# i2-mb_rpi.net
KiCad netlist of a schematic drawn in EAGLE
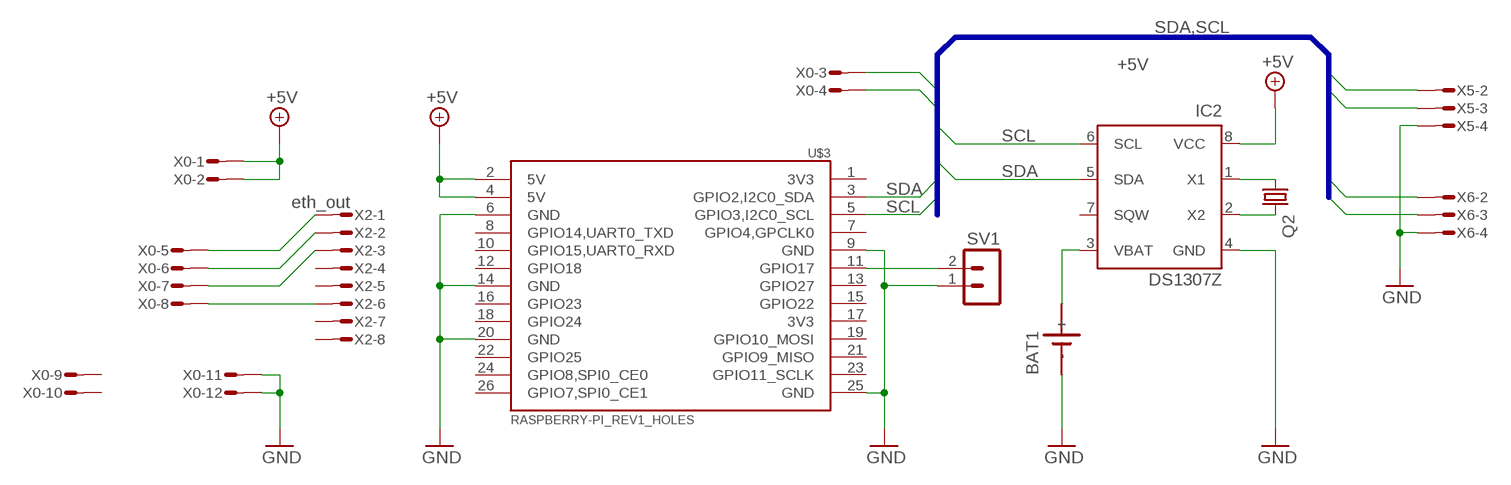
[diagram p0: schematic, sheet 1]

(export (version "E")
  (design (tool "Eeschema 10.0.6"))
  (components
    (comp (ref "BAT1")
      (value "SN2032")
      (footprint "eagle-import:SN2032")
      (libsource (lib "eagle-import") (part "SN2032"))
    )
    (comp (ref "IC2")
      (value "DS1307Z")
      (footprint "eagle-import:SOIC8")
      (libsource (lib "eagle-import") (part "DS1307Z"))
    )
    (comp (ref "Q2")
      (value "CRYSTAL")
      (footprint "eagle-import:CFPX-217")
      (libsource (lib "eagle-import") (part "CRYSTAL"))
    )
    (comp (ref "SV1")
      (value "MA02-1")
      (footprint "eagle-import:MA03-1")
      (libsource (lib "eagle-import") (part "MA02-1"))
    )
    (comp (ref "U$3")
      (value "RASPBERRY-PI_REV1_HOLES")
      (footprint "eagle-import:RASPBERRY-PI_REV1_HOLES")
      (libsource (lib "eagle-import") (part "RASPBERRY-PI_REV1_HOLES"))
    )
    (comp (ref "X0")
      (value "MICROMATCH-12")
      (footprint "eagle-import:MICROMATCH-12")
      (libsource (lib "eagle-import") (part "MICROMATCH-12"))
    )
    (comp (ref "X2")
      (value "eth_out")
      (footprint "eagle-import:MICROMATCH-8")
      (libsource (lib "eagle-import") (part "MICROMATCH-8"))
    )
    (comp (ref "X5")
      (value "i2c#1")
      (footprint "eagle-import:MICROMATCH-4")
      (libsource (lib "eagle-import") (part "MICROMATCH-4"))
    )
    (comp (ref "X6")
      (value "i2c#2")
      (footprint "eagle-import:MICROMATCH-4")
      (libsource (lib "eagle-import") (part "MICROMATCH-4"))
    )
  )
  (nets
    (net (code "1") (name "+5V") (class "Default")
      (node (ref "IC2") (pin "8") (pinfunction "VCC_8") (pintype "power_in"))
      (node (ref "U$3") (pin "2") (pinfunction "5V_2") (pintype "bidirectional"))
      (node (ref "U$3") (pin "4") (pinfunction "5V_4") (pintype "bidirectional"))
      (node (ref "X0") (pin "1") (pinfunction "S_1") (pintype "passive"))
      (node (ref "X0") (pin "2") (pinfunction "S_2") (pintype "passive"))
    )
    (net (code "2") (name "/SCL") (class "Default")
      (node (ref "IC2") (pin "6") (pinfunction "SCL_6") (pintype "input"))
      (node (ref "U$3") (pin "5") (pinfunction "GPIO3,I2C0_SCL_5") (pintype "bidirectional"))
      (node (ref "X0") (pin "4") (pinfunction "S_4") (pintype "passive"))
      (node (ref "X5") (pin "3") (pinfunction "S_3") (pintype "passive"))
      (node (ref "X6") (pin "3") (pinfunction "S_3") (pintype "passive"))
    )
    (net (code "3") (name "/SDA") (class "Default")
      (node (ref "IC2") (pin "5") (pinfunction "SDA_5") (pintype "bidirectional"))
      (node (ref "U$3") (pin "3") (pinfunction "GPIO2,I2C0_SDA_3") (pintype "bidirectional"))
      (node (ref "X0") (pin "3") (pinfunction "S_3") (pintype "passive"))
      (node (ref "X5") (pin "2") (pinfunction "S_2") (pintype "passive"))
      (node (ref "X6") (pin "2") (pinfunction "S_2") (pintype "passive"))
    )
    (net (code "5") (name "GND") (class "Default")
      (node (ref "BAT1") (pin "-") (pinfunction "-_-") (pintype "passive"))
      (node (ref "IC2") (pin "4") (pinfunction "GND_4") (pintype "power_in"))
      (node (ref "SV1") (pin "1") (pinfunction "1_1") (pintype "passive"))
      (node (ref "U$3") (pin "14") (pinfunction "GND_14") (pintype "bidirectional"))
      (node (ref "U$3") (pin "20") (pinfunction "GND_20") (pintype "bidirectional"))
      (node (ref "U$3") (pin "25") (pinfunction "GND_25") (pintype "bidirectional"))
      (node (ref "U$3") (pin "6") (pinfunction "GND_6") (pintype "bidirectional"))
      (node (ref "U$3") (pin "9") (pinfunction "GND_9") (pintype "bidirectional"))
      (node (ref "X0") (pin "11") (pinfunction "S_11") (pintype "passive"))
      (node (ref "X0") (pin "12") (pinfunction "S_12") (pintype "passive"))
      (node (ref "X5") (pin "4") (pinfunction "S_4") (pintype "passive"))
      (node (ref "X6") (pin "4") (pinfunction "S_4") (pintype "passive"))
    )
    (net (code "6") (name "Net-(IC2-VBAT)") (class "Default")
      (node (ref "BAT1") (pin "+") (pinfunction "+_+") (pintype "passive"))
      (node (ref "IC2") (pin "3") (pinfunction "VBAT_3") (pintype "passive"))
    )
    (net (code "7") (name "Net-(IC2-X1)") (class "Default")
      (node (ref "IC2") (pin "1") (pinfunction "X1_1") (pintype "input"))
      (node (ref "Q2") (pin "1") (pinfunction "1_1") (pintype "passive"))
    )
    (net (code "8") (name "Net-(IC2-X2)") (class "Default")
      (node (ref "IC2") (pin "2") (pinfunction "X2_2") (pintype "output"))
      (node (ref "Q2") (pin "2") (pinfunction "2_2") (pintype "passive"))
    )
    (net (code "9") (name "Net-(U$3-GPIO17)") (class "Default")
      (node (ref "SV1") (pin "2") (pinfunction "2_2") (pintype "passive"))
      (node (ref "U$3") (pin "11") (pinfunction "GPIO17_11") (pintype "bidirectional"))
    )
    (net (code "10") (name "Net-(X0H-S)") (class "Default")
      (node (ref "X0") (pin "5") (pinfunction "S_5") (pintype "passive"))
      (node (ref "X2") (pin "1") (pinfunction "S_1") (pintype "passive"))
    )
    (net (code "11") (name "Net-(X0I-S)") (class "Default")
      (node (ref "X0") (pin "6") (pinfunction "S_6") (pintype "passive"))
      (node (ref "X2") (pin "2") (pinfunction "S_2") (pintype "passive"))
    )
    (net (code "12") (name "Net-(X0J-S)") (class "Default")
      (node (ref "X0") (pin "7") (pinfunction "S_7") (pintype "passive"))
      (node (ref "X2") (pin "3") (pinfunction "S_3") (pintype "passive"))
    )
    (net (code "13") (name "Net-(X0K-S)") (class "Default")
      (node (ref "X0") (pin "8") (pinfunction "S_8") (pintype "passive"))
      (node (ref "X2") (pin "6") (pinfunction "S_6") (pintype "passive"))
    )
    (net (code "14") (name "unconnected-(IC2-SQW-Pad7)") (class "Default")
      (node (ref "IC2") (pin "7") (pinfunction "SQW_7") (pintype "open_collector"))
    )
    (net (code "15") (name "unconnected-(U$3-3V3-Pad1)") (class "Default")
      (node (ref "U$3") (pin "1") (pinfunction "3V3_1") (pintype "bidirectional"))
    )
    (net (code "16") (name "unconnected-(U$3-3V3-Pad17)") (class "Default")
      (node (ref "U$3") (pin "17") (pinfunction "3V3_17") (pintype "bidirectional"))
    )
    (net (code "17") (name "unconnected-(U$3-GPIO4,GPCLK0-Pad7)") (class "Default")
      (node (ref "U$3") (pin "7") (pinfunction "GPIO4,GPCLK0_7") (pintype "bidirectional"))
    )
    (net (code "18") (name "unconnected-(U$3-GPIO7,SPI0_CE1-Pad26)") (class "Default")
      (node (ref "U$3") (pin "26") (pinfunction "GPIO7,SPI0_CE1_26") (pintype "bidirectional"))
    )
    (net (code "19") (name "unconnected-(U$3-GPIO8,SPI0_CE0-Pad24)") (class "Default")
      (node (ref "U$3") (pin "24") (pinfunction "GPIO8,SPI0_CE0_24") (pintype "bidirectional"))
    )
    (net (code "20") (name "unconnected-(U$3-GPIO9_MISO-Pad21)") (class "Default")
      (node (ref "U$3") (pin "21") (pinfunction "GPIO9_MISO_21") (pintype "bidirectional"))
    )
    (net (code "21") (name "unconnected-(U$3-GPIO10_MOSI-Pad19)") (class "Default")
      (node (ref "U$3") (pin "19") (pinfunction "GPIO10_MOSI_19") (pintype "bidirectional"))
    )
    (net (code "22") (name "unconnected-(U$3-GPIO11_SCLK-Pad23)") (class "Default")
      (node (ref "U$3") (pin "23") (pinfunction "GPIO11_SCLK_23") (pintype "bidirectional"))
    )
    (net (code "23") (name "unconnected-(U$3-GPIO14,UART0_TXD-Pad8)") (class "Default")
      (node (ref "U$3") (pin "8") (pinfunction "GPIO14,UART0_TXD_8") (pintype "bidirectional"))
    )
    (net (code "24") (name "unconnected-(U$3-GPIO15,UART0_RXD-Pad10)") (class "Default")
      (node (ref "U$3") (pin "10") (pinfunction "GPIO15,UART0_RXD_10") (pintype "bidirectional"))
    )
    (net (code "25") (name "unconnected-(U$3-GPIO18-Pad12)") (class "Default")
      (node (ref "U$3") (pin "12") (pinfunction "GPIO18_12") (pintype "bidirectional"))
    )
    (net (code "26") (name "unconnected-(U$3-GPIO22-Pad15)") (class "Default")
      (node (ref "U$3") (pin "15") (pinfunction "GPIO22_15") (pintype "bidirectional"))
    )
    (net (code "27") (name "unconnected-(U$3-GPIO23-Pad16)") (class "Default")
      (node (ref "U$3") (pin "16") (pinfunction "GPIO23_16") (pintype "bidirectional"))
    )
    (net (code "28") (name "unconnected-(U$3-GPIO24-Pad18)") (class "Default")
      (node (ref "U$3") (pin "18") (pinfunction "GPIO24_18") (pintype "bidirectional"))
    )
    (net (code "29") (name "unconnected-(U$3-GPIO25-Pad22)") (class "Default")
      (node (ref "U$3") (pin "22") (pinfunction "GPIO25_22") (pintype "bidirectional"))
    )
    (net (code "30") (name "unconnected-(U$3-GPIO27-Pad13)") (class "Default")
      (node (ref "U$3") (pin "13") (pinfunction "GPIO27_13") (pintype "bidirectional"))
    )
    (net (code "31") (name "unconnected-(X0B-S-Pad10)") (class "Default")
      (node (ref "X0") (pin "10") (pinfunction "S_10") (pintype "passive"))
    )
    (net (code "32") (name "unconnected-(X0L-S-Pad9)") (class "Default")
      (node (ref "X0") (pin "9") (pinfunction "S_9") (pintype "passive"))
    )
    (net (code "33") (name "unconnected-(X2D-S-Pad4)") (class "Default")
      (node (ref "X2") (pin "4") (pinfunction "S_4") (pintype "passive"))
    )
    (net (code "34") (name "unconnected-(X2E-S-Pad5)") (class "Default")
      (node (ref "X2") (pin "5") (pinfunction "S_5") (pintype "passive"))
    )
    (net (code "35") (name "unconnected-(X2G-S-Pad7)") (class "Default")
      (node (ref "X2") (pin "7") (pinfunction "S_7") (pintype "passive"))
    )
    (net (code "36") (name "unconnected-(X2H-S-Pad8)") (class "Default")
      (node (ref "X2") (pin "8") (pinfunction "S_8") (pintype "passive"))
    )
  )
)
